# BUCK_5v_TPS54340_P-MOS.net
KiCad netlist of a schematic drawn in Altium Designer
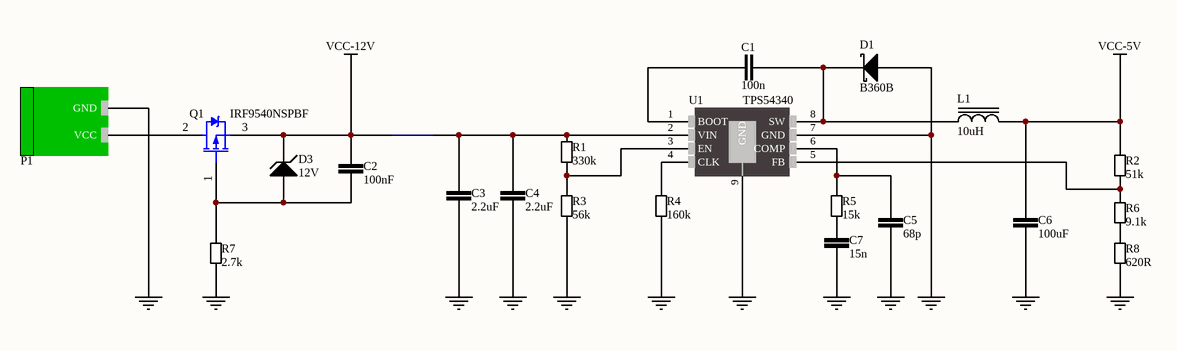
[diagram p0: BUCK_5v_TPS54340_P-MOS.SchDoc]

(export (version "E")
  (design (tool "Eeschema 10.0.6"))
  (components
    (comp (ref "C1")
      (value "100n")
      (footprint "CER_0603")
      (description "CAP CER 100n 10V X5R 10% 0603")
      (libsource (lib "Capacitors") (part "06032105"))
    )
    (comp (ref "C2")
      (value "100nF")
      (footprint "CER_0805")
      (description "CAP CER 100n 50V X7R 10% 0805")
      (libsource (lib "Capacitors") (part "00002105"))
    )
    (comp (ref "C3")
      (value "2.2uF")
      (footprint "CER_1210")
      (description "CAP CER 2.2u")
      (libsource (lib "Capacitors") (part "00001225"))
    )
    (comp (ref "C4")
      (value "2.2uF")
      (footprint "CER_1210")
      (description "CAP CER 2.2u")
      (libsource (lib "Capacitors") (part "00001225"))
    )
    (comp (ref "C5")
      (value "68p")
      (footprint "CER_0603")
      (description "CAP CER 68p 0603")
      (libsource (lib "Capacitors") (part "06032680"))
    )
    (comp (ref "C6")
      (value "100uF")
      (footprint "CER_1210")
      (description "CAP CER 100u X5R 6.3V 10% 1210")
      (libsource (lib "Capacitors") (part "00002108"))
    )
    (comp (ref "C7")
      (value "15n")
      (footprint "CER_0603")
      (description "CAP CER 15n 0603")
      (libsource (lib "Capacitors") (part "06032153"))
    )
    (comp (ref "D1")
      (value "B360B")
      (footprint "DO214AC")
      (description "DIODE SCHOTTKY 60V 3A DO214AC")
      (fields (field (name "MANUFACTURER") "Vishay Semiconductor Diodes Division"))
      (libsource (lib "Discrete_Semiconductor") (part "B360B"))
    )
    (comp (ref "D3")
      (value "12V")
      (footprint "DO214AC")
      (description "DIODE ZENER")
      (fields
        (field (name "MANUFACTURER") "Vishay Semiconductor Diodes Division")
        (field (name "MANUFACTURER PART NUMBER") "B360B")
      )
      (libsource (lib "Discrete_Semiconductor") (part "ZENER"))
    )
    (comp (ref "L1")
      (value "10uH")
      (footprint "INDUCTOR_SS1260-103MLD")
      (description "FIXED IND 10uH 5.3A")
      (fields
        (field (name "MANUFACTURER") "Coilcraft")
        (field (name "MANUFACTURER PART NUMBER") "XAL7030-103MEB")
      )
      (libsource (lib "Discrete_Semiconductor") (part "Inductor_10uH"))
    )
    (comp (ref "P1")
      (value "2EDGRC-5.08-02P-14-00A(H)")
      (footprint "PWR_Con")
      (description "TERM BLOCK HDR 2POS 90DEG 5.08MM")
      (libsource (lib "Electro_Mechanical") (part "00000002"))
    )
    (comp (ref "Q1")
      (value "IRF9540NSPBF")
      (footprint "D2PAK-2")
      (description "P-MOS")
      (fields (field (name "MANUFACTURER") "INTERNATIONAL RECTIFIER"))
      (libsource (lib "Discrete_Semiconductor") (part "IRF9540N"))
    )
    (comp (ref "R1")
      (value "330k")
      (footprint "RESC2013X38N-0805-NOOVERLAY")
      (description "RES SMD 330 kOhm 1/8W 0805")
      (fields (field (name "POWER") "0.125W, 1/8W"))
      (libsource (lib "Resistors") (part "00003303"))
    )
    (comp (ref "R2")
      (value "51k")
      (footprint "RESC2013X38N-0805-NOOVERLAY")
      (description "RES SMD 51 kOhm 1/8W 0805")
      (fields (field (name "POWER") "0.125W, 1/8W"))
      (libsource (lib "Resistors") (part "00005102"))
    )
    (comp (ref "R3")
      (value "56k")
      (footprint "RESC2013X38N-0805-NOOVERLAY")
      (description "RES SMD 56 kOhm 1/8W 0805")
      (fields (field (name "POWER") "0.125W, 1/8W"))
      (libsource (lib "Resistors") (part "00005602"))
    )
    (comp (ref "R4")
      (value "160k")
      (footprint "RESC2013X38N-0805-NOOVERLAY")
      (description "RES SMD 160 kOhm 1/8W 0805")
      (fields (field (name "POWER") "0.125W, 1/8W"))
      (libsource (lib "Resistors") (part "00001603"))
    )
    (comp (ref "R5")
      (value "15k")
      (footprint "RESC2013X38N-0805-NOOVERLAY")
      (description "RES SMD 15 kOhm 1/8W 0805")
      (fields (field (name "POWER") "0.125W, 1/8W"))
      (libsource (lib "Resistors") (part "00001502"))
    )
    (comp (ref "R6")
      (value "9.1k")
      (footprint "RESC2013X38N-0805-NOOVERLAY")
      (description "RES SMD 9.1 kOhm 1/8W 0805")
      (fields (field (name "POWER") "0.125W, 1/8W"))
      (libsource (lib "Resistors") (part "00009101"))
    )
    (comp (ref "R7")
      (value "2.7k")
      (footprint "RESC2013X38N-0805-NOOVERLAY")
      (description "RES SMD 2.7 kOhm 1/8W 0805")
      (fields (field (name "POWER") "0.125W, 1/8W"))
      (libsource (lib "Resistors") (part "00002701"))
    )
    (comp (ref "R8")
      (value "620R")
      (footprint "RESC2013X38N-0805-NOOVERLAY")
      (description "RES SMD 620 Ohm 1/8W 0805")
      (fields (field (name "POWER") "0.125W, 1/8W"))
      (libsource (lib "Resistors") (part "00006200"))
    )
    (comp (ref "U1")
      (value "TPS54340")
      (footprint "HSOP-8")
      (description "IC REG BUCK ADJ 3.5A 8SOPWRPAD")
      (libsource (lib "Integrated_circuits") (part "TPS54340"))
    )
  )
  (nets
    (net (code "1") (name "GND") (class "Default")
      (node (ref "C3") (pin "1") (pinfunction "1_1") (pintype "passive"))
      (node (ref "C4") (pin "1") (pinfunction "1_1") (pintype "passive"))
      (node (ref "C5") (pin "1") (pinfunction "1_1") (pintype "passive"))
      (node (ref "C6") (pin "1") (pinfunction "1_1") (pintype "passive"))
      (node (ref "C7") (pin "1") (pinfunction "1_1") (pintype "passive"))
      (node (ref "D1") (pin "2") (pinfunction "Anode_2") (pintype "passive"))
      (node (ref "P1") (pin "1") (pinfunction "GND_1") (pintype "passive"))
      (node (ref "R3") (pin "1") (pinfunction "1_1") (pintype "passive"))
      (node (ref "R4") (pin "1") (pinfunction "1_1") (pintype "passive"))
      (node (ref "R7") (pin "1") (pinfunction "1_1") (pintype "passive"))
      (node (ref "R8") (pin "1") (pinfunction "1_1") (pintype "passive"))
      (node (ref "U1") (pin "7") (pinfunction "GND_7") (pintype "passive"))
      (node (ref "U1") (pin "9") (pinfunction "GND_9") (pintype "passive"))
    )
    (net (code "2") (name "Net-(C7-Pad2)") (class "Default")
      (node (ref "C7") (pin "2") (pinfunction "2_2") (pintype "passive"))
      (node (ref "R5") (pin "1") (pinfunction "1_1") (pintype "passive"))
    )
    (net (code "3") (name "Net-(D1-Cathode)") (class "Default")
      (node (ref "C1") (pin "2") (pinfunction "2_2") (pintype "passive"))
      (node (ref "D1") (pin "1") (pinfunction "Cathode_1") (pintype "passive"))
      (node (ref "L1") (pin "1") (pinfunction "1_1") (pintype "passive"))
      (node (ref "U1") (pin "8") (pinfunction "SW_8") (pintype "passive"))
    )
    (net (code "4") (name "Net-(D3-Anode)") (class "Default")
      (node (ref "C2") (pin "1") (pinfunction "1_1") (pintype "passive"))
      (node (ref "D3") (pin "2") (pinfunction "Anode_2") (pintype "passive"))
      (node (ref "Q1") (pin "1") (pinfunction "G_1") (pintype "passive"))
      (node (ref "R7") (pin "2") (pinfunction "2_2") (pintype "passive"))
    )
    (net (code "5") (name "Net-(P1-VCC)") (class "Default")
      (node (ref "P1") (pin "2") (pinfunction "VCC_2") (pintype "passive"))
      (node (ref "Q1") (pin "2") (pinfunction "D_2") (pintype "passive"))
    )
    (net (code "6") (name "Net-(R6-Pad1)") (class "Default")
      (node (ref "R6") (pin "1") (pinfunction "1_1") (pintype "passive"))
      (node (ref "R8") (pin "2") (pinfunction "2_2") (pintype "passive"))
    )
    (net (code "7") (name "Net-(U1-BOOT)") (class "Default")
      (node (ref "C1") (pin "1") (pinfunction "1_1") (pintype "passive"))
      (node (ref "U1") (pin "1") (pinfunction "BOOT_1") (pintype "passive"))
    )
    (net (code "8") (name "Net-(U1-CLK)") (class "Default")
      (node (ref "R4") (pin "2") (pinfunction "2_2") (pintype "passive"))
      (node (ref "U1") (pin "4") (pinfunction "CLK_4") (pintype "passive"))
    )
    (net (code "9") (name "Net-(U1-COMP)") (class "Default")
      (node (ref "C5") (pin "2") (pinfunction "2_2") (pintype "passive"))
      (node (ref "R5") (pin "2") (pinfunction "2_2") (pintype "passive"))
      (node (ref "U1") (pin "6") (pinfunction "COMP_6") (pintype "passive"))
    )
    (net (code "10") (name "Net-(U1-EN)") (class "Default")
      (node (ref "R1") (pin "1") (pinfunction "1_1") (pintype "passive"))
      (node (ref "R3") (pin "2") (pinfunction "2_2") (pintype "passive"))
      (node (ref "U1") (pin "3") (pinfunction "EN_3") (pintype "passive"))
    )
    (net (code "11") (name "Net-(U1-FB)") (class "Default")
      (node (ref "R2") (pin "1") (pinfunction "1_1") (pintype "passive"))
      (node (ref "R6") (pin "2") (pinfunction "2_2") (pintype "passive"))
      (node (ref "U1") (pin "5") (pinfunction "FB_5") (pintype "passive"))
    )
    (net (code "12") (name "VCC-5V") (class "Default")
      (node (ref "C6") (pin "2") (pinfunction "2_2") (pintype "passive"))
      (node (ref "L1") (pin "2") (pinfunction "2_2") (pintype "passive"))
      (node (ref "R2") (pin "2") (pinfunction "2_2") (pintype "passive"))
    )
    (net (code "13") (name "VCC-12V") (class "Default")
      (node (ref "C2") (pin "2") (pinfunction "2_2") (pintype "passive"))
      (node (ref "C3") (pin "2") (pinfunction "2_2") (pintype "passive"))
      (node (ref "C4") (pin "2") (pinfunction "2_2") (pintype "passive"))
      (node (ref "D3") (pin "1") (pinfunction "Cathode_1") (pintype "passive"))
      (node (ref "Q1") (pin "3") (pinfunction "S_3") (pintype "passive"))
      (node (ref "R1") (pin "2") (pinfunction "2_2") (pintype "passive"))
      (node (ref "U1") (pin "2") (pinfunction "VIN_2") (pintype "passive"))
    )
  )
)
